# SCH_drone-smt-3-high-power_2022-06-06.net
KiCad netlist of a schematic drawn in EasyEDA
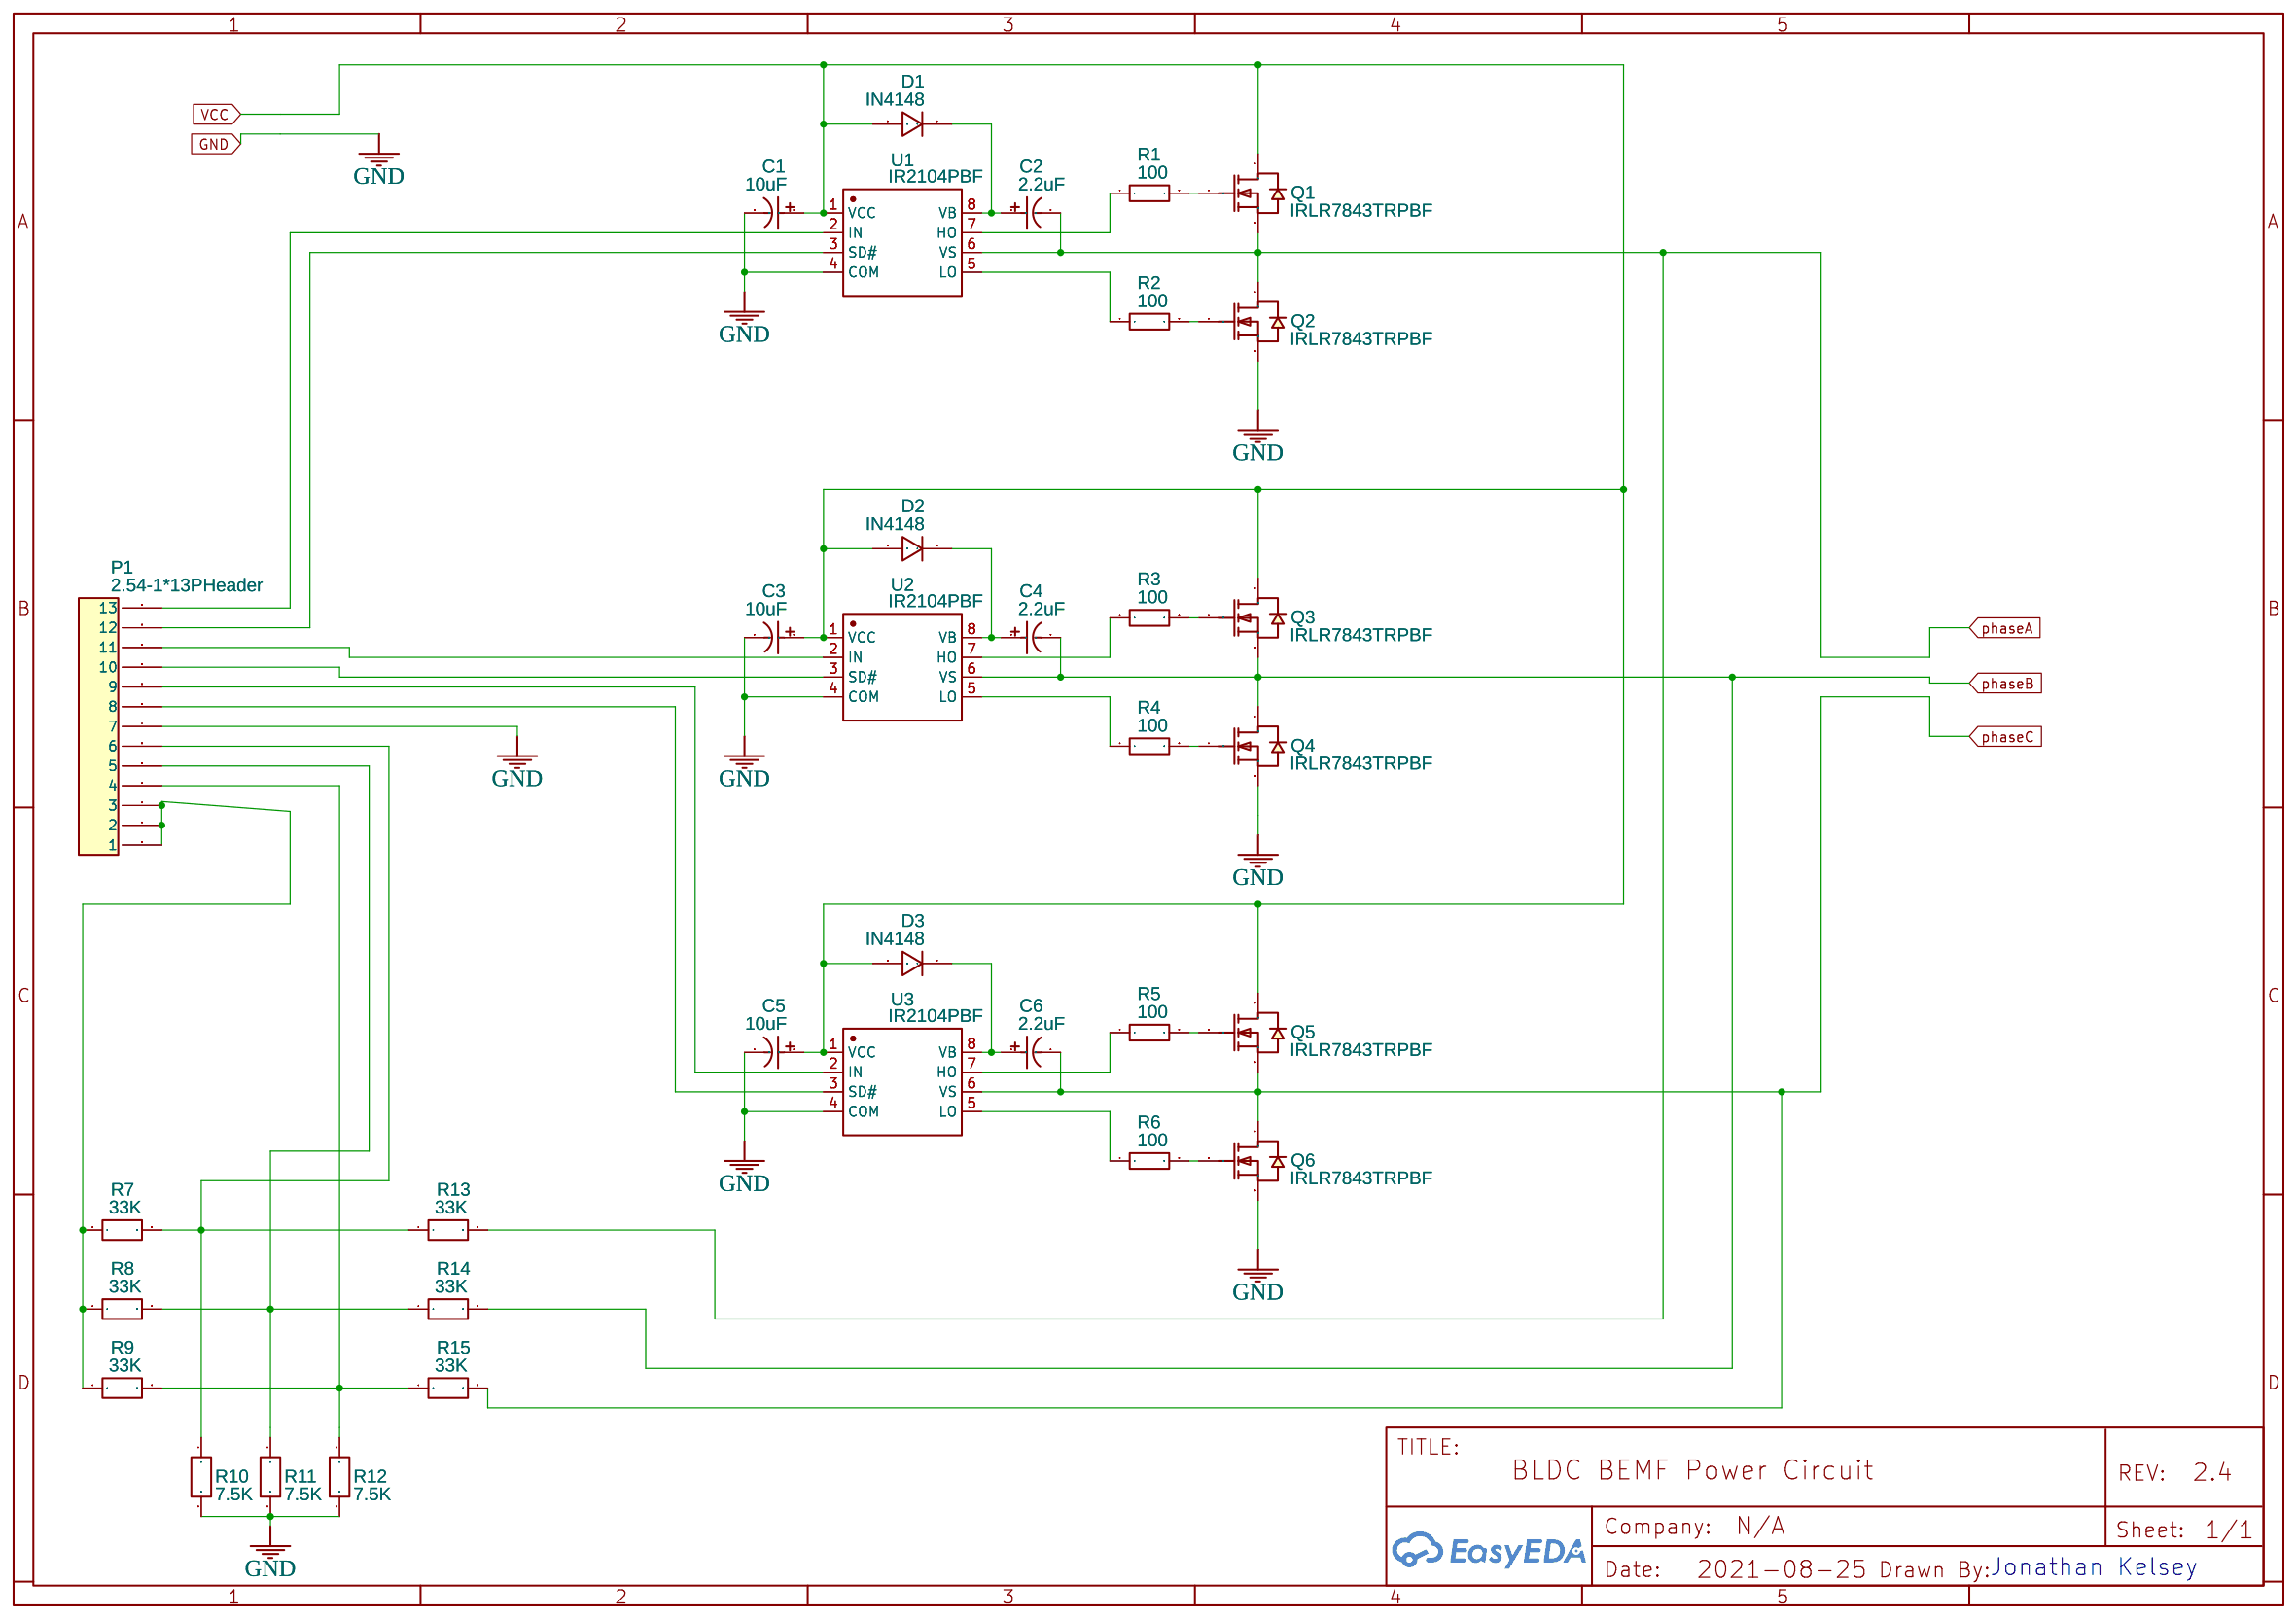
[diagram p0: schematic sheet]

(export (version "E")
  (design (tool "Eeschema 10.0.6"))
  (components
    (comp (ref "C1")
      (value "10uF")
      (fields
        (field (name "BOM_Manufacturer Part") "10uF 50V 5*11")
        (field (name "BOM_Supplier Part") "C43345")
      )
      (libsource (lib "") (part "10uF 50V 5*11"))
    )
    (comp (ref "C2")
      (value "2.2uF")
      (fields (field (name "BOM_Manufacturer Part") "2.2uf/50V") (field (name "BOM_Supplier Part") "C2065"))
      (libsource (lib "") (part "2.2uf/50V"))
    )
    (comp (ref "C3")
      (value "10uF")
      (fields
        (field (name "BOM_Manufacturer Part") "10uF 50V 5*11")
        (field (name "BOM_Supplier Part") "C43345")
      )
      (libsource (lib "") (part "10uF 50V 5*11"))
    )
    (comp (ref "C4")
      (value "2.2uF")
      (fields (field (name "BOM_Manufacturer Part") "2.2uf/50V") (field (name "BOM_Supplier Part") "C2065"))
      (libsource (lib "") (part "2.2uf/50V"))
    )
    (comp (ref "C5")
      (value "10uF")
      (fields
        (field (name "BOM_Manufacturer Part") "10uF 50V 5*11")
        (field (name "BOM_Supplier Part") "C43345")
      )
      (libsource (lib "") (part "10uF 50V 5*11"))
    )
    (comp (ref "C6")
      (value "2.2uF")
      (fields (field (name "BOM_Manufacturer Part") "2.2uf/50V") (field (name "BOM_Supplier Part") "C2065"))
      (libsource (lib "") (part "2.2uf/50V"))
    )
    (comp (ref "D1")
      (value "IN4148")
      (fields (field (name "BOM_Supplier Part") "C14538"))
      (libsource (lib "") (part "IN4148"))
    )
    (comp (ref "D2")
      (value "IN4148")
      (fields (field (name "BOM_Supplier Part") "C14538"))
      (libsource (lib "") (part "IN4148"))
    )
    (comp (ref "D3")
      (value "IN4148")
      (fields (field (name "BOM_Supplier Part") "C14538"))
      (libsource (lib "") (part "IN4148"))
    )
    (comp (ref "P1")
      (value "2.54-1*13PHeader")
      (fields (field (name "BOM_Supplier Part") "C52928"))
      (libsource (lib "") (part "2.54-1*13PHeader"))
    )
    (comp (ref "Q1")
      (value "IRLR7843TRPBF")
      (fields (field (name "BOM_Supplier Part") "C21988"))
      (libsource (lib "") (part "IRLR7843TRPBF"))
    )
    (comp (ref "Q2")
      (value "IRLR7843TRPBF")
      (fields (field (name "BOM_Supplier Part") "C21988"))
      (libsource (lib "") (part "IRLR7843TRPBF"))
    )
    (comp (ref "Q3")
      (value "IRLR7843TRPBF")
      (fields (field (name "BOM_Supplier Part") "C21988"))
      (libsource (lib "") (part "IRLR7843TRPBF"))
    )
    (comp (ref "Q4")
      (value "IRLR7843TRPBF")
      (fields (field (name "BOM_Supplier Part") "C21988"))
      (libsource (lib "") (part "IRLR7843TRPBF"))
    )
    (comp (ref "Q5")
      (value "IRLR7843TRPBF")
      (fields (field (name "BOM_Supplier Part") "C21988"))
      (libsource (lib "") (part "IRLR7843TRPBF"))
    )
    (comp (ref "Q6")
      (value "IRLR7843TRPBF")
      (fields (field (name "BOM_Supplier Part") "C21988"))
      (libsource (lib "") (part "IRLR7843TRPBF"))
    )
    (comp (ref "R1")
      (value "100")
      (fields (field (name "BOM_Supplier Part") "C119407"))
      (libsource (lib "") (part "MF1/2W-100Ω±1% T52"))
    )
    (comp (ref "R2")
      (value "100")
      (fields (field (name "BOM_Supplier Part") "C119407"))
      (libsource (lib "") (part "MF1/2W-100Ω±1% T52"))
    )
    (comp (ref "R3")
      (value "100")
      (fields (field (name "BOM_Supplier Part") "C119407"))
      (libsource (lib "") (part "MF1/2W-100Ω±1% T52"))
    )
    (comp (ref "R4")
      (value "100")
      (fields (field (name "BOM_Supplier Part") "C119407"))
      (libsource (lib "") (part "MF1/2W-100Ω±1% T52"))
    )
    (comp (ref "R5")
      (value "100")
      (fields (field (name "BOM_Supplier Part") "C119407"))
      (libsource (lib "") (part "MF1/2W-100Ω±1% T52"))
    )
    (comp (ref "R6")
      (value "100")
      (fields (field (name "BOM_Supplier Part") "C119407"))
      (libsource (lib "") (part "MF1/2W-100Ω±1% T52"))
    )
    (comp (ref "R7")
      (value "33K")
      (fields
        (field (name "BOM_Manufacturer Part") "RN 1WS 33K F T/B A1")
        (field (name "BOM_Supplier Part") "C433632")
      )
      (libsource (lib "") (part "RN 1WS 33K F T/B A1"))
    )
    (comp (ref "R8")
      (value "33K")
      (fields
        (field (name "BOM_Manufacturer Part") "RN 1WS 33K F T/B A1")
        (field (name "BOM_Supplier Part") "C433632")
      )
      (libsource (lib "") (part "RN 1WS 33K F T/B A1"))
    )
    (comp (ref "R9")
      (value "33K")
      (fields
        (field (name "BOM_Manufacturer Part") "RN 1WS 33K F T/B A1")
        (field (name "BOM_Supplier Part") "C433632")
      )
      (libsource (lib "") (part "RN 1WS 33K F T/B A1"))
    )
    (comp (ref "R10")
      (value "7.5K")
      (fields
        (field (name "BOM_Manufacturer Part") "RN1/2W7.5KΩFT/BA1")
        (field (name "BOM_Supplier Part") "C385665")
      )
      (libsource (lib "") (part "RN1/2W7.5KΩFT/BA1"))
    )
    (comp (ref "R11")
      (value "7.5K")
      (fields
        (field (name "BOM_Manufacturer Part") "RN1/2W7.5KΩFT/BA1")
        (field (name "BOM_Supplier Part") "C385665")
      )
      (libsource (lib "") (part "RN1/2W7.5KΩFT/BA1"))
    )
    (comp (ref "R12")
      (value "7.5K")
      (fields
        (field (name "BOM_Manufacturer Part") "RN1/2W7.5KΩFT/BA1")
        (field (name "BOM_Supplier Part") "C385665")
      )
      (libsource (lib "") (part "RN1/2W7.5KΩFT/BA1"))
    )
    (comp (ref "R13")
      (value "33K")
      (fields
        (field (name "BOM_Manufacturer Part") "RN 1WS 33K F T/B A1")
        (field (name "BOM_Supplier Part") "C433632")
      )
      (libsource (lib "") (part "RN 1WS 33K F T/B A1"))
    )
    (comp (ref "R14")
      (value "33K")
      (fields
        (field (name "BOM_Manufacturer Part") "RN 1WS 33K F T/B A1")
        (field (name "BOM_Supplier Part") "C433632")
      )
      (libsource (lib "") (part "RN 1WS 33K F T/B A1"))
    )
    (comp (ref "R15")
      (value "33K")
      (fields
        (field (name "BOM_Manufacturer Part") "RN 1WS 33K F T/B A1")
        (field (name "BOM_Supplier Part") "C433632")
      )
      (libsource (lib "") (part "RN 1WS 33K F T/B A1"))
    )
    (comp (ref "U1")
      (value "IR2104PBF")
      (fields (field (name "BOM_Supplier Part") "C2959"))
      (libsource (lib "") (part "IR2104PBF"))
    )
    (comp (ref "U2")
      (value "IR2104PBF")
      (fields (field (name "BOM_Supplier Part") "C2959"))
      (libsource (lib "") (part "IR2104PBF"))
    )
    (comp (ref "U3")
      (value "IR2104PBF")
      (fields (field (name "BOM_Supplier Part") "C2959"))
      (libsource (lib "") (part "IR2104PBF"))
    )
  )
  (nets
    (net (code "1") (name "GND") (class "Default")
      (node (ref "C1") (pin "2") (pinfunction "2_2") (pintype "input"))
      (node (ref "C3") (pin "2") (pinfunction "2_2") (pintype "input"))
      (node (ref "C5") (pin "2") (pinfunction "2_2") (pintype "input"))
      (node (ref "P1") (pin "7") (pinfunction "7_7") (pintype "input"))
      (node (ref "Q2") (pin "3") (pinfunction "S_3") (pintype "unspecified"))
      (node (ref "Q4") (pin "3") (pinfunction "S_3") (pintype "unspecified"))
      (node (ref "Q6") (pin "3") (pinfunction "S_3") (pintype "unspecified"))
      (node (ref "R10") (pin "2") (pinfunction "2_2") (pintype "unspecified"))
      (node (ref "R11") (pin "2") (pinfunction "2_2") (pintype "unspecified"))
      (node (ref "R12") (pin "2") (pinfunction "2_2") (pintype "unspecified"))
      (node (ref "U1") (pin "4") (pinfunction "COM_4") (pintype "unspecified"))
      (node (ref "U2") (pin "4") (pinfunction "COM_4") (pintype "unspecified"))
      (node (ref "U3") (pin "4") (pinfunction "COM_4") (pintype "unspecified"))
    )
    (net (code "2") (name "Net-(P1-Pad1)") (class "Default")
      (node (ref "P1") (pin "1") (pinfunction "1_1") (pintype "input"))
      (node (ref "P1") (pin "2") (pinfunction "2_2") (pintype "input"))
      (node (ref "P1") (pin "3") (pinfunction "3_3") (pintype "input"))
      (node (ref "R7") (pin "1") (pinfunction "1_1") (pintype "unspecified"))
      (node (ref "R8") (pin "1") (pinfunction "1_1") (pintype "unspecified"))
      (node (ref "R9") (pin "1") (pinfunction "1_1") (pintype "unspecified"))
    )
    (net (code "3") (name "Net-(P1-Pad4)") (class "Default")
      (node (ref "P1") (pin "4") (pinfunction "4_4") (pintype "input"))
      (node (ref "R12") (pin "1") (pinfunction "1_1") (pintype "unspecified"))
      (node (ref "R15") (pin "1") (pinfunction "1_1") (pintype "unspecified"))
      (node (ref "R9") (pin "2") (pinfunction "2_2") (pintype "unspecified"))
    )
    (net (code "4") (name "Net-(P1-Pad5)") (class "Default")
      (node (ref "P1") (pin "5") (pinfunction "5_5") (pintype "input"))
      (node (ref "R11") (pin "1") (pinfunction "1_1") (pintype "unspecified"))
      (node (ref "R14") (pin "1") (pinfunction "1_1") (pintype "unspecified"))
      (node (ref "R8") (pin "2") (pinfunction "2_2") (pintype "unspecified"))
    )
    (net (code "5") (name "Net-(P1-Pad6)") (class "Default")
      (node (ref "P1") (pin "6") (pinfunction "6_6") (pintype "input"))
      (node (ref "R10") (pin "1") (pinfunction "1_1") (pintype "unspecified"))
      (node (ref "R13") (pin "1") (pinfunction "1_1") (pintype "unspecified"))
      (node (ref "R7") (pin "2") (pinfunction "2_2") (pintype "unspecified"))
    )
    (net (code "6") (name "Net-(Q1-G)") (class "Default")
      (node (ref "Q1") (pin "1") (pinfunction "G_1") (pintype "unspecified"))
      (node (ref "R1") (pin "2") (pinfunction "2_2") (pintype "unspecified"))
    )
    (net (code "7") (name "Net-(Q2-G)") (class "Default")
      (node (ref "Q2") (pin "1") (pinfunction "G_1") (pintype "unspecified"))
      (node (ref "R2") (pin "2") (pinfunction "2_2") (pintype "unspecified"))
    )
    (net (code "8") (name "Net-(Q3-G)") (class "Default")
      (node (ref "Q3") (pin "1") (pinfunction "G_1") (pintype "unspecified"))
      (node (ref "R3") (pin "2") (pinfunction "2_2") (pintype "unspecified"))
    )
    (net (code "9") (name "Net-(Q4-G)") (class "Default")
      (node (ref "Q4") (pin "1") (pinfunction "G_1") (pintype "unspecified"))
      (node (ref "R4") (pin "2") (pinfunction "2_2") (pintype "unspecified"))
    )
    (net (code "10") (name "Net-(Q5-G)") (class "Default")
      (node (ref "Q5") (pin "1") (pinfunction "G_1") (pintype "unspecified"))
      (node (ref "R5") (pin "2") (pinfunction "2_2") (pintype "unspecified"))
    )
    (net (code "11") (name "Net-(Q6-G)") (class "Default")
      (node (ref "Q6") (pin "1") (pinfunction "G_1") (pintype "unspecified"))
      (node (ref "R6") (pin "2") (pinfunction "2_2") (pintype "unspecified"))
    )
    (net (code "12") (name "Net-(U1-HO)") (class "Default")
      (node (ref "R1") (pin "1") (pinfunction "1_1") (pintype "unspecified"))
      (node (ref "U1") (pin "7") (pinfunction "HO_7") (pintype "unspecified"))
    )
    (net (code "13") (name "Net-(U1-IN)") (class "Default")
      (node (ref "P1") (pin "13") (pinfunction "13_13") (pintype "input"))
      (node (ref "U1") (pin "2") (pinfunction "IN_2") (pintype "unspecified"))
    )
    (net (code "14") (name "Net-(U1-LO)") (class "Default")
      (node (ref "R2") (pin "1") (pinfunction "1_1") (pintype "unspecified"))
      (node (ref "U1") (pin "5") (pinfunction "LO_5") (pintype "unspecified"))
    )
    (net (code "15") (name "Net-(U1-SD#)") (class "Default")
      (node (ref "P1") (pin "12") (pinfunction "12_12") (pintype "input"))
      (node (ref "U1") (pin "3") (pinfunction "SD#_3") (pintype "unspecified"))
    )
    (net (code "16") (name "Net-(U1-VB)") (class "Default")
      (node (ref "C2") (pin "1") (pinfunction "1_1") (pintype "input"))
      (node (ref "D1") (pin "1") (pinfunction "1_1") (pintype "unspecified"))
      (node (ref "U1") (pin "8") (pinfunction "VB_8") (pintype "unspecified"))
    )
    (net (code "17") (name "Net-(U2-HO)") (class "Default")
      (node (ref "R3") (pin "1") (pinfunction "1_1") (pintype "unspecified"))
      (node (ref "U2") (pin "7") (pinfunction "HO_7") (pintype "unspecified"))
    )
    (net (code "18") (name "Net-(U2-IN)") (class "Default")
      (node (ref "P1") (pin "11") (pinfunction "11_11") (pintype "input"))
      (node (ref "U2") (pin "2") (pinfunction "IN_2") (pintype "unspecified"))
    )
    (net (code "19") (name "Net-(U2-LO)") (class "Default")
      (node (ref "R4") (pin "1") (pinfunction "1_1") (pintype "unspecified"))
      (node (ref "U2") (pin "5") (pinfunction "LO_5") (pintype "unspecified"))
    )
    (net (code "20") (name "Net-(U2-SD#)") (class "Default")
      (node (ref "P1") (pin "10") (pinfunction "10_10") (pintype "input"))
      (node (ref "U2") (pin "3") (pinfunction "SD#_3") (pintype "unspecified"))
    )
    (net (code "21") (name "Net-(U2-VB)") (class "Default")
      (node (ref "C4") (pin "1") (pinfunction "1_1") (pintype "input"))
      (node (ref "D2") (pin "1") (pinfunction "1_1") (pintype "unspecified"))
      (node (ref "U2") (pin "8") (pinfunction "VB_8") (pintype "unspecified"))
    )
    (net (code "22") (name "Net-(U3-HO)") (class "Default")
      (node (ref "R5") (pin "1") (pinfunction "1_1") (pintype "unspecified"))
      (node (ref "U3") (pin "7") (pinfunction "HO_7") (pintype "unspecified"))
    )
    (net (code "23") (name "Net-(U3-IN)") (class "Default")
      (node (ref "P1") (pin "9") (pinfunction "9_9") (pintype "input"))
      (node (ref "U3") (pin "2") (pinfunction "IN_2") (pintype "unspecified"))
    )
    (net (code "24") (name "Net-(U3-LO)") (class "Default")
      (node (ref "R6") (pin "1") (pinfunction "1_1") (pintype "unspecified"))
      (node (ref "U3") (pin "5") (pinfunction "LO_5") (pintype "unspecified"))
    )
    (net (code "25") (name "Net-(U3-SD#)") (class "Default")
      (node (ref "P1") (pin "8") (pinfunction "8_8") (pintype "input"))
      (node (ref "U3") (pin "3") (pinfunction "SD#_3") (pintype "unspecified"))
    )
    (net (code "26") (name "Net-(U3-VB)") (class "Default")
      (node (ref "C6") (pin "1") (pinfunction "1_1") (pintype "input"))
      (node (ref "D3") (pin "1") (pinfunction "1_1") (pintype "unspecified"))
      (node (ref "U3") (pin "8") (pinfunction "VB_8") (pintype "unspecified"))
    )
    (net (code "27") (name "VCC") (class "Default")
      (node (ref "C1") (pin "1") (pinfunction "1_1") (pintype "input"))
      (node (ref "C3") (pin "1") (pinfunction "1_1") (pintype "input"))
      (node (ref "C5") (pin "1") (pinfunction "1_1") (pintype "input"))
      (node (ref "D1") (pin "2") (pinfunction "2_2") (pintype "unspecified"))
      (node (ref "D2") (pin "2") (pinfunction "2_2") (pintype "unspecified"))
      (node (ref "D3") (pin "2") (pinfunction "2_2") (pintype "unspecified"))
      (node (ref "Q1") (pin "4") (pinfunction "D_4") (pintype "unspecified"))
      (node (ref "Q3") (pin "4") (pinfunction "D_4") (pintype "unspecified"))
      (node (ref "Q5") (pin "4") (pinfunction "D_4") (pintype "unspecified"))
      (node (ref "U1") (pin "1") (pinfunction "VCC_1") (pintype "unspecified"))
      (node (ref "U2") (pin "1") (pinfunction "VCC_1") (pintype "unspecified"))
      (node (ref "U3") (pin "1") (pinfunction "VCC_1") (pintype "unspecified"))
    )
    (net (code "28") (name "phaseA") (class "Default")
      (node (ref "C2") (pin "2") (pinfunction "2_2") (pintype "input"))
      (node (ref "Q1") (pin "3") (pinfunction "S_3") (pintype "unspecified"))
      (node (ref "Q2") (pin "4") (pinfunction "D_4") (pintype "unspecified"))
      (node (ref "R13") (pin "2") (pinfunction "2_2") (pintype "unspecified"))
      (node (ref "U1") (pin "6") (pinfunction "VS_6") (pintype "unspecified"))
    )
    (net (code "29") (name "phaseB") (class "Default")
      (node (ref "C4") (pin "2") (pinfunction "2_2") (pintype "input"))
      (node (ref "Q3") (pin "3") (pinfunction "S_3") (pintype "unspecified"))
      (node (ref "Q4") (pin "4") (pinfunction "D_4") (pintype "unspecified"))
      (node (ref "R14") (pin "2") (pinfunction "2_2") (pintype "unspecified"))
      (node (ref "U2") (pin "6") (pinfunction "VS_6") (pintype "unspecified"))
    )
    (net (code "30") (name "phaseC") (class "Default")
      (node (ref "C6") (pin "2") (pinfunction "2_2") (pintype "input"))
      (node (ref "Q5") (pin "3") (pinfunction "S_3") (pintype "unspecified"))
      (node (ref "Q6") (pin "4") (pinfunction "D_4") (pintype "unspecified"))
      (node (ref "R15") (pin "2") (pinfunction "2_2") (pintype "unspecified"))
      (node (ref "U3") (pin "6") (pinfunction "VS_6") (pintype "unspecified"))
    )
  )
)
